# RF_MODULE.net
KiCad netlist of a schematic drawn in Altium Designer
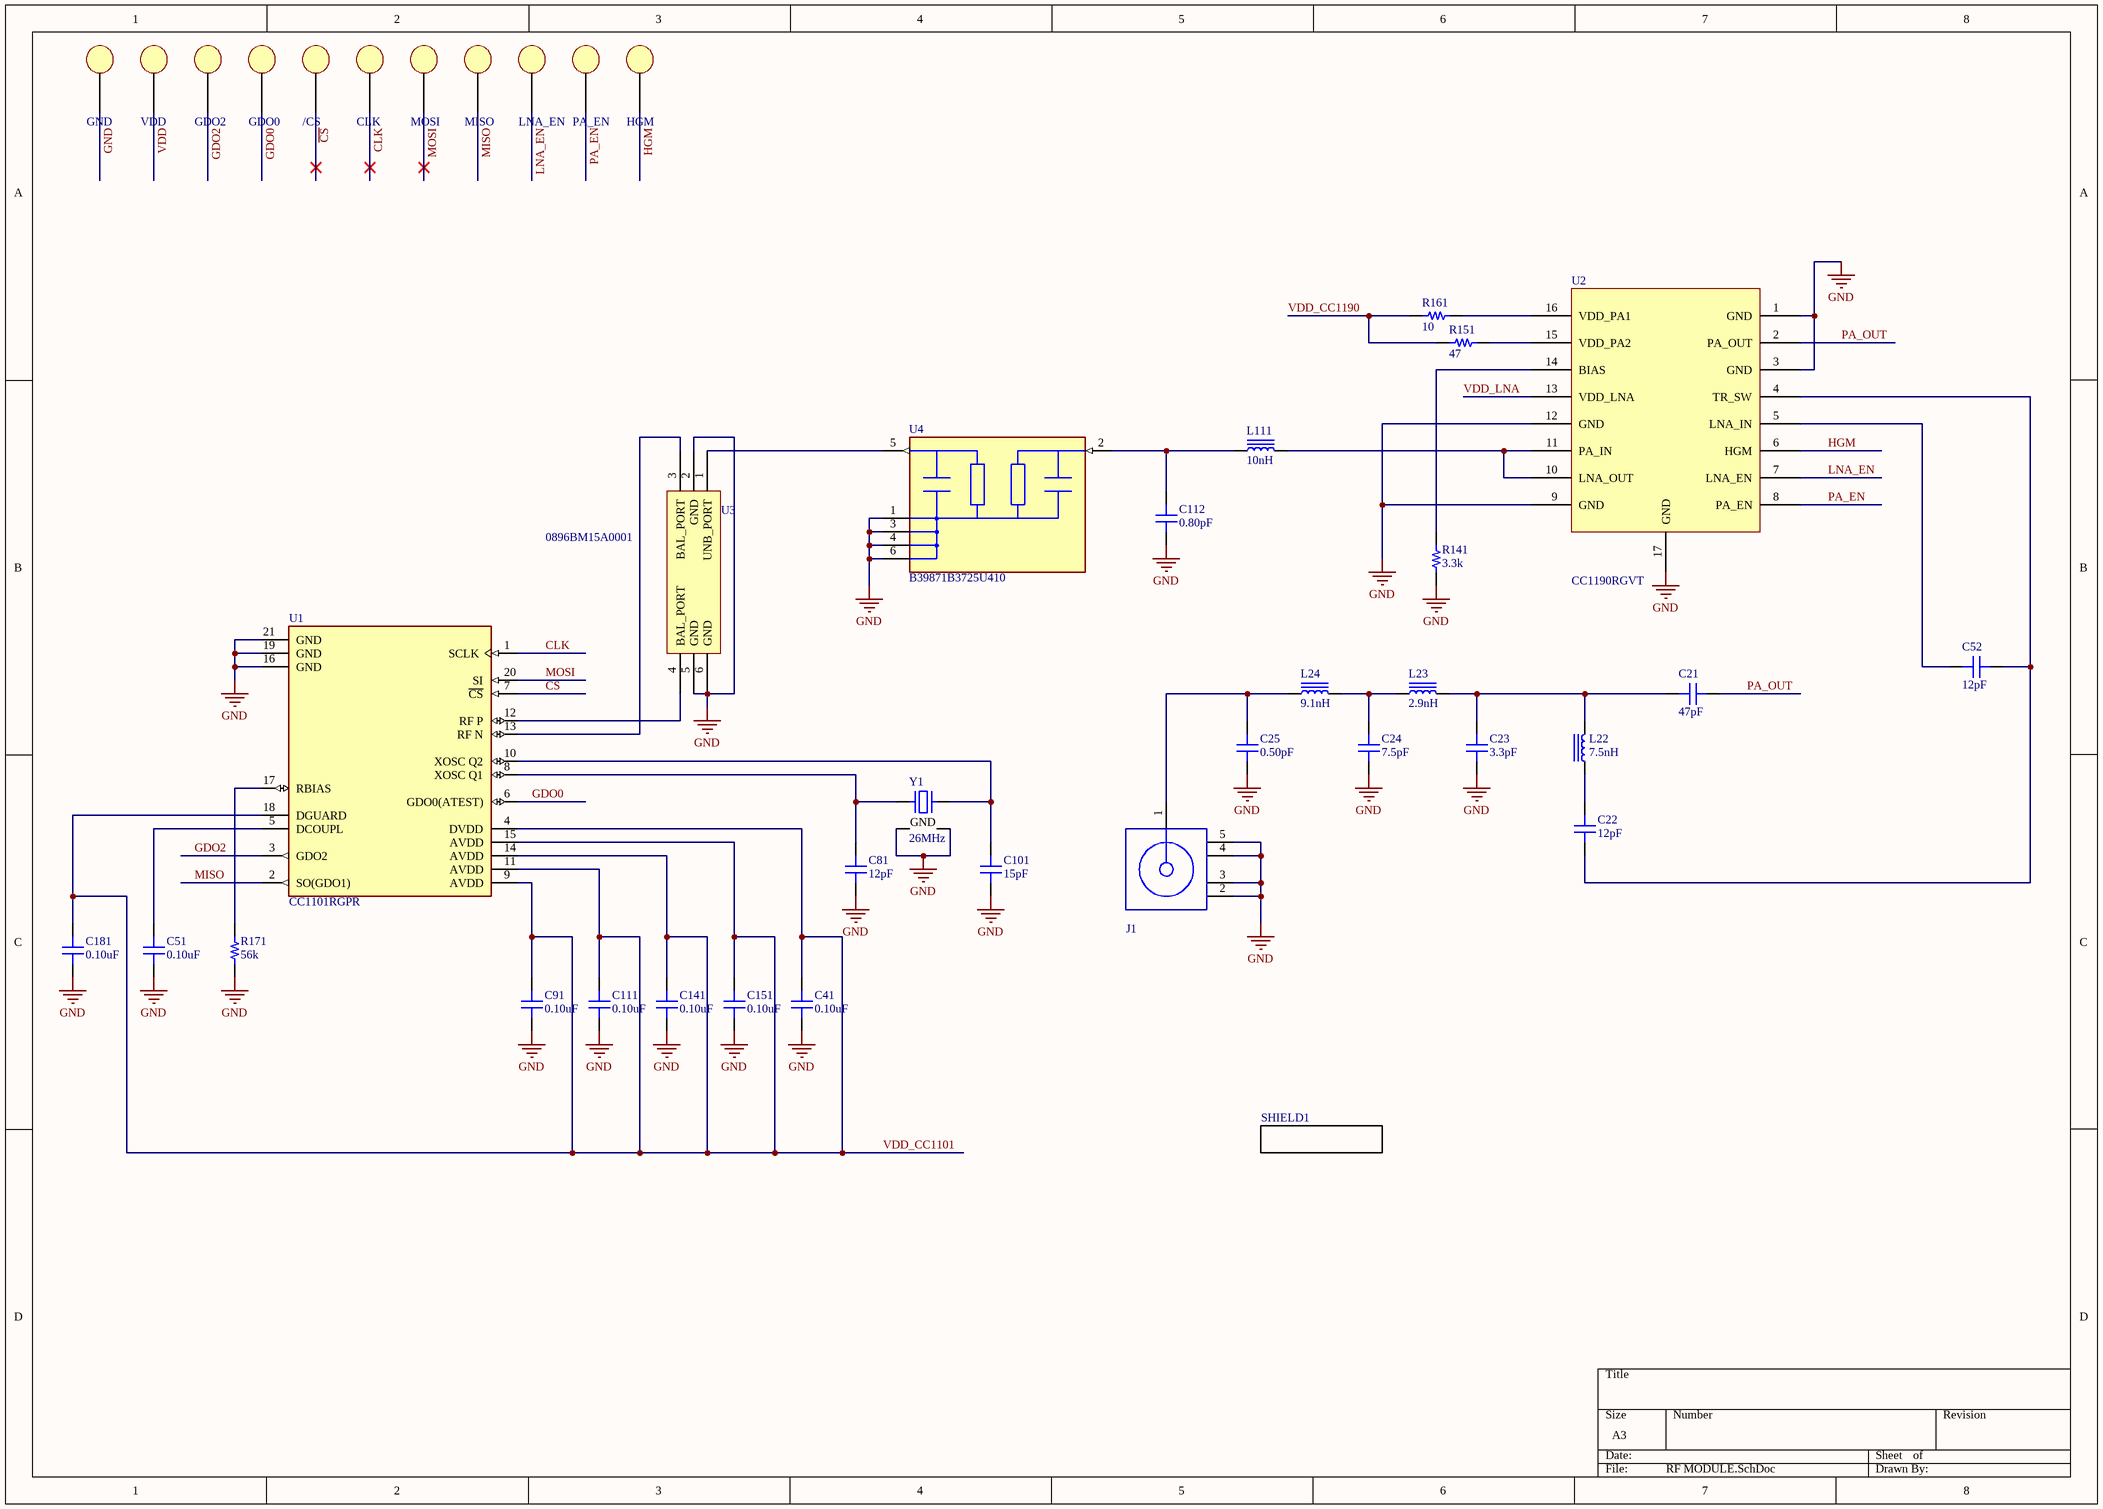
[diagram p0: RF MODULE.SchDoc]

(export (version "E")
  (design (tool "Eeschema 10.0.6"))
  (components
    (comp (ref "/CS")
      (value "Castellation")
      (footprint "Castellation")
      (libsource (lib "MyLibrary") (part "Castellation"))
    )
    (comp (ref "C21")
      (value "47pF")
      (footprint "CAP 0402/1005")
      (description "CAP CER 47PF 50V NP0 0402")
      (fields
        (field (name "PART NUMBER") "GRM1555C1H470JA01D")
        (field (name "MANUFACTURER") "Murata Electronics North America")
      )
      (libsource (lib "Celestial Library Database") (part "Capacitor"))
    )
    (comp (ref "C22")
      (value "12pF")
      (footprint "CAP 0402/1005")
      (description "CAP CER 12PF 50V NP0 0402")
      (fields
        (field (name "PART NUMBER") "GRM1555C1H120JA01D")
        (field (name "MANUFACTURER") "Murata Electronics North America")
      )
      (libsource (lib "Celestial Library Database") (part "Capacitor"))
    )
    (comp (ref "C23")
      (value "3.3pF")
      (footprint "CAP 0402/1005")
      (description "CAP CER 3.3PF 50V NP0 0402")
      (fields
        (field (name "PART NUMBER") "GRM1555C1H3R3CA01D")
        (field (name "MANUFACTURER") "Murata Electronics North America")
      )
      (libsource (lib "Celestial Library Database") (part "Capacitor"))
    )
    (comp (ref "C24")
      (value "7.5pF")
      (footprint "CAP 0402/1005")
      (description "CAP CER 7.5PF 50V NP0 0402")
      (fields
        (field (name "PART NUMBER") "GRM1555C1H7R5CA01D")
        (field (name "MANUFACTURER") "Murata Electronics North America")
      )
      (libsource (lib "Celestial Library Database") (part "Capacitor"))
    )
    (comp (ref "C25")
      (value "0.50pF")
      (footprint "CAP 0402/1005")
      (description "CAP CER 0.50PF 50V NP0 0402")
      (fields
        (field (name "PART NUMBER") "GRM1555C1HR50BA01D")
        (field (name "MANUFACTURER") "Murata Electronics North America")
      )
      (libsource (lib "Celestial Library Database") (part "Capacitor"))
    )
    (comp (ref "C41")
      (value "0.10uF")
      (footprint "CAP 0402/1005")
      (description "CAP CER 0.1UF 10V X5R 0402")
      (fields
        (field (name "PART NUMBER") "GRM152R61A104KE19D")
        (field (name "MANUFACTURER") "Murata Electronics North America")
      )
      (libsource (lib "Celestial Library Database") (part "Capacitor"))
    )
    (comp (ref "C51")
      (value "0.10uF")
      (footprint "CAP 0402/1005")
      (description "CAP CER 0.1UF 10V X5R 0402")
      (fields
        (field (name "PART NUMBER") "GRM152R61A104KE19D")
        (field (name "MANUFACTURER") "Murata Electronics North America")
      )
      (libsource (lib "Celestial Library Database") (part "Capacitor"))
    )
    (comp (ref "C52")
      (value "12pF")
      (footprint "CAP 0402/1005")
      (description "CAP CER 12PF 50V NP0 0402")
      (fields
        (field (name "PART NUMBER") "GRM1555C1H120FA01D")
        (field (name "MANUFACTURER") "Murata Electronics North America")
      )
      (libsource (lib "Celestial Library Database") (part "Capacitor"))
    )
    (comp (ref "C81")
      (value "12pF")
      (footprint "CAP 0402/1005")
      (description "CAP CER 12PF 50V NP0 0402")
      (fields
        (field (name "PART NUMBER") "GRM1555C1H120JA01D")
        (field (name "MANUFACTURER") "Murata Electronics North America")
      )
      (libsource (lib "Celestial Library Database") (part "Capacitor"))
    )
    (comp (ref "C91")
      (value "0.10uF")
      (footprint "CAP 0402/1005")
      (description "CAP CER 0.1UF 10V X5R 0402")
      (fields
        (field (name "PART NUMBER") "GRM152R61A104KE19D")
        (field (name "MANUFACTURER") "Murata Electronics North America")
      )
      (libsource (lib "Celestial Library Database") (part "Capacitor"))
    )
    (comp (ref "C101")
      (value "15pF")
      (footprint "CAP 0402/1005")
      (description "CAP CER 15PF 50V NP0 0402")
      (fields
        (field (name "PART NUMBER") "GRM1555C1H150JA01D")
        (field (name "MANUFACTURER") "Murata Electronics North America")
      )
      (libsource (lib "Celestial Library Database") (part "Capacitor"))
    )
    (comp (ref "C111")
      (value "0.10uF")
      (footprint "CAP 0402/1005")
      (description "CAP CER 0.1UF 10V X5R 0402")
      (fields
        (field (name "PART NUMBER") "GRM152R61A104KE19D")
        (field (name "MANUFACTURER") "Murata Electronics North America")
      )
      (libsource (lib "Celestial Library Database") (part "Capacitor"))
    )
    (comp (ref "C112")
      (value "0.80pF")
      (footprint "CAP 0402/1005")
      (description "CAP CER 0.80PF 50V NP0 0402")
      (fields
        (field (name "PART NUMBER") "GRM1555C1HR80BA01D")
        (field (name "MANUFACTURER") "Murata Electronics North America")
      )
      (libsource (lib "Celestial Library Database") (part "Capacitor"))
    )
    (comp (ref "C141")
      (value "0.10uF")
      (footprint "CAP 0402/1005")
      (description "CAP CER 0.1UF 10V X5R 0402")
      (fields
        (field (name "PART NUMBER") "GRM152R61A104KE19D")
        (field (name "MANUFACTURER") "Murata Electronics North America")
      )
      (libsource (lib "Celestial Library Database") (part "Capacitor"))
    )
    (comp (ref "C151")
      (value "0.10uF")
      (footprint "CAP 0402/1005")
      (description "CAP CER 0.1UF 10V X5R 0402")
      (fields
        (field (name "PART NUMBER") "GRM152R61A104KE19D")
        (field (name "MANUFACTURER") "Murata Electronics North America")
      )
      (libsource (lib "Celestial Library Database") (part "Capacitor"))
    )
    (comp (ref "C181")
      (value "0.10uF")
      (footprint "CAP 0402/1005")
      (description "CAP CER 0.1UF 10V X5R 0402")
      (fields
        (field (name "PART NUMBER") "GRM152R61A104KE19D")
        (field (name "MANUFACTURER") "Murata Electronics North America")
      )
      (libsource (lib "Celestial Library Database") (part "Capacitor"))
    )
    (comp (ref "CLK")
      (value "Castellation")
      (footprint "Castellation")
      (libsource (lib "MyLibrary") (part "Castellation"))
    )
    (comp (ref "GDO0")
      (value "Castellation")
      (footprint "Castellation")
      (libsource (lib "MyLibrary") (part "Castellation"))
    )
    (comp (ref "GDO2")
      (value "Castellation")
      (footprint "Castellation")
      (libsource (lib "MyLibrary") (part "Castellation"))
    )
    (comp (ref "GND")
      (value "Castellation")
      (footprint "Castellation")
      (libsource (lib "MyLibrary") (part "Castellation"))
    )
    (comp (ref "HGM")
      (value "Castellation")
      (footprint "Castellation")
      (libsource (lib "MyLibrary") (part "Castellation"))
    )
    (comp (ref "J1")
      (value "73251-1150")
      (footprint "Molex_73251-1150_0")
      (description "SMA socket")
      (libsource (lib "MyLibrary") (part "73251-1150"))
    )
    (comp (ref "L22")
      (value "7.5nH")
      (footprint "IND 0402/1005 RF WW")
      (description "FIXED IND 7.5NH 570MA 130 MOHM")
      (fields
        (field (name "PART NUMBER") "LQW15AN7N5G00D")
        (field (name "MANUFACTURER") "Murata Electronics North America")
      )
      (libsource (lib "Celestial Library Database") (part "Inductor"))
    )
    (comp (ref "L23")
      (value "2.9nH")
      (footprint "IND 0402/1005 RF WW")
      (description "FIXED IND 2.9NH 750MA 70 MOHM")
      (fields
        (field (name "PART NUMBER") "LQW15AN2N9B00D")
        (field (name "MANUFACTURER") "Murata Electronics North America")
      )
      (libsource (lib "Celestial Library Database") (part "Inductor"))
    )
    (comp (ref "L24")
      (value "9.1nH")
      (footprint "IND 0402/1005 RF WW")
      (description "FIXED IND 9.1NH 540MA 140 MOHM")
      (fields
        (field (name "PART NUMBER") "LQW15AN9N1G00D")
        (field (name "MANUFACTURER") "Murata Electronics North America")
      )
      (libsource (lib "Celestial Library Database") (part "Inductor"))
    )
    (comp (ref "L111")
      (value "10nH")
      (footprint "IND 0402/1005 RF WW")
      (description "FIXED IND 10NH 500MA 170 MOHM")
      (fields
        (field (name "PART NUMBER") "LQW15AN10NG00D")
        (field (name "MANUFACTURER") "Murata Electronics North America")
      )
      (libsource (lib "Celestial Library Database") (part "Inductor"))
    )
    (comp (ref "LNA_EN")
      (value "Castellation")
      (footprint "Castellation")
      (libsource (lib "MyLibrary") (part "Castellation"))
    )
    (comp (ref "MISO")
      (value "Castellation")
      (footprint "Castellation")
      (libsource (lib "MyLibrary") (part "Castellation"))
    )
    (comp (ref "MOSI")
      (value "Castellation")
      (footprint "Castellation")
      (libsource (lib "MyLibrary") (part "Castellation"))
    )
    (comp (ref "PA_EN")
      (value "Castellation")
      (footprint "Castellation")
      (libsource (lib "MyLibrary") (part "Castellation"))
    )
    (comp (ref "R141")
      (value "3.3k")
      (footprint "RES 0402/1005")
      (description "RES SMD 3.3K OHM 1% 1/10W 0402")
      (fields
        (field (name "PART NUMBER") "ERJ-2RKF3301X")
        (field (name "MANUFACTURER") "Panasonic Electronic Components")
      )
      (libsource (lib "Celestial Library Database") (part "Resistor"))
    )
    (comp (ref "R151")
      (value "47")
      (footprint "RES 0402/1005")
      (description "RES SMD 47 OHM 1% 1/10W 0402")
      (fields
        (field (name "PART NUMBER") "ERJ-2RKF47R0X")
        (field (name "MANUFACTURER") "Panasonic Electronic Components")
      )
      (libsource (lib "Celestial Library Database") (part "Resistor"))
    )
    (comp (ref "R161")
      (value "10")
      (footprint "RES 0402/1005")
      (description "RES SMD 10 OHM 1% 1/10W 0402")
      (fields
        (field (name "PART NUMBER") "ERJ-2RKF10R0X")
        (field (name "MANUFACTURER") "Panasonic Electronic Components")
      )
      (libsource (lib "Celestial Library Database") (part "Resistor"))
    )
    (comp (ref "R171")
      (value "56k")
      (footprint "RES 0402/1005")
      (description "RES SMD 56K OHM 1% 1/10W 0402")
      (fields
        (field (name "PART NUMBER") "ERJ-2RKF5602X")
        (field (name "MANUFACTURER") "Panasonic Electronic Components")
      )
      (libsource (lib "Celestial Library Database") (part "Resistor"))
    )
    (comp (ref "SHIELD1")
      (value "SMS-202F")
      (footprint "SMS-202F")
      (description "RF Shield Frame 0.650\" (16.51mm) X 0.650\" (16.51mm) Surface Mount")
      (fields (field (name "MF") "Laird"))
      (libsource (lib "MyLibrary") (part "SMS-202F"))
    )
    (comp (ref "U1")
      (value "CC1101RGPR")
      (footprint "Texas_Instruments_RGP0020C_0")
      (description "Low-Power Sub-1GHz RF Transceiver 20-QFN -40 to 85")
      (libsource (lib "MyLibrary") (part "CC1101RGPR"))
    )
    (comp (ref "U2")
      (value "CC1190RGVT")
      (footprint "QFN65P400X400X100_HS-17N")
      (description "LNA/PA RF Front End 6.2dB 11.6dB/27.9dB 16-Pin VQFN EP T/R")
      (libsource (lib "MyLibrary") (part "CC1190RGVT"))
    )
    (comp (ref "U3")
      (value "0896BM15A0001")
      (footprint "0896BM15A0001")
      (description "868/915 MHz Impedance Matched/Balun/LPF Integrated Component")
      (libsource (lib "MyLibrary") (part "0896BM15A0001"))
    )
    (comp (ref "U4")
      (value "Filter_TDK_B39871B3725U410_eec")
      (footprint "TDK_B39871B3725U410_0")
      (description "FILTER SAW 869.0MHZ SMD")
      (fields
        (field (name "MANUFACTURER") "TDK")
        (field (name "MOUSER PART NUMBER") "871-B39871B3725U410")
        (field (name "PART NUMBER") "B39871B3725U410")
      )
      (libsource (lib "MyLibrary") (part "Filter_TDK_B39871B3725U410_eec"))
    )
    (comp (ref "VDD")
      (value "Castellation")
      (footprint "Castellation")
      (libsource (lib "MyLibrary") (part "Castellation"))
    )
    (comp (ref "Y1")
      (value "26MHz")
      (footprint "NDK NX2520SA")
      (description "CRYSTAL 26.0000MHZ 10PF SMD")
      (fields (field (name "PART NUMBER") "NX2520SA-26.000000MHZ") (field (name "MANUFACTURER") "NDK"))
      (libsource (lib "Celestial Library Database") (part "NDK Crystal NX2520SA"))
    )
  )
  (nets
    (net (code "1") (name "/CLK") (class "Default")
      (node (ref "CLK") (pin "PIN") (pinfunction "PIN_PIN") (pintype "passive"))
      (node (ref "U1") (pin "1") (pinfunction "SCLK_1") (pintype "input"))
    )
    (net (code "2") (name "/GDO0") (class "Default")
      (node (ref "GDO0") (pin "PIN") (pinfunction "PIN_PIN") (pintype "passive"))
      (node (ref "U1") (pin "6") (pinfunction "GDO0(ATEST)_6") (pintype "bidirectional"))
    )
    (net (code "3") (name "/GDO2") (class "Default")
      (node (ref "GDO2") (pin "PIN") (pinfunction "PIN_PIN") (pintype "passive"))
      (node (ref "U1") (pin "3") (pinfunction "GDO2_3") (pintype "output"))
    )
    (net (code "4") (name "/HGM") (class "Default")
      (node (ref "HGM") (pin "PIN") (pinfunction "PIN_PIN") (pintype "passive"))
      (node (ref "U2") (pin "6") (pinfunction "HGM_6") (pintype "passive"))
    )
    (net (code "5") (name "/LNA_EN") (class "Default")
      (node (ref "LNA_EN") (pin "PIN") (pinfunction "PIN_PIN") (pintype "passive"))
      (node (ref "U2") (pin "7") (pinfunction "LNA_EN_7") (pintype "passive"))
    )
    (net (code "6") (name "/MISO") (class "Default")
      (node (ref "MISO") (pin "PIN") (pinfunction "PIN_PIN") (pintype "passive"))
      (node (ref "U1") (pin "2") (pinfunction "SO(GDO1)_2") (pintype "output"))
    )
    (net (code "7") (name "/MOSI") (class "Default")
      (node (ref "MOSI") (pin "PIN") (pinfunction "PIN_PIN") (pintype "passive"))
      (node (ref "U1") (pin "20") (pinfunction "SI_20") (pintype "input"))
    )
    (net (code "8") (name "/PA_EN") (class "Default")
      (node (ref "PA_EN") (pin "PIN") (pinfunction "PIN_PIN") (pintype "passive"))
      (node (ref "U2") (pin "8") (pinfunction "PA_EN_8") (pintype "passive"))
    )
    (net (code "9") (name "/PA_OUT") (class "Default")
      (node (ref "C21") (pin "2") (pinfunction "2_2") (pintype "passive"))
      (node (ref "U2") (pin "2") (pinfunction "PA_OUT_2") (pintype "passive"))
    )
    (net (code "10") (name "/VDD") (class "Default")
      (node (ref "VDD") (pin "PIN") (pinfunction "PIN_PIN") (pintype "passive"))
    )
    (net (code "11") (name "/VDD_CC1101") (class "Default")
      (node (ref "C111") (pin "2") (pinfunction "2_2") (pintype "passive"))
      (node (ref "C141") (pin "2") (pinfunction "2_2") (pintype "passive"))
      (node (ref "C151") (pin "2") (pinfunction "2_2") (pintype "passive"))
      (node (ref "C181") (pin "2") (pinfunction "2_2") (pintype "passive"))
      (node (ref "C41") (pin "2") (pinfunction "2_2") (pintype "passive"))
      (node (ref "C91") (pin "2") (pinfunction "2_2") (pintype "passive"))
      (node (ref "U1") (pin "11") (pinfunction "AVDD_11") (pintype "power_in"))
      (node (ref "U1") (pin "14") (pinfunction "AVDD_14") (pintype "power_in"))
      (node (ref "U1") (pin "15") (pinfunction "AVDD_15") (pintype "power_in"))
      (node (ref "U1") (pin "18") (pinfunction "DGUARD_18") (pintype "power_in"))
      (node (ref "U1") (pin "4") (pinfunction "DVDD_4") (pintype "power_in"))
      (node (ref "U1") (pin "9") (pinfunction "AVDD_9") (pintype "power_in"))
    )
    (net (code "12") (name "/VDD_CC1190") (class "Default")
      (node (ref "R151") (pin "1") (pinfunction "1_1") (pintype "passive"))
      (node (ref "R161") (pin "1") (pinfunction "1_1") (pintype "passive"))
    )
    (net (code "13") (name "/VDD_LNA") (class "Default")
      (node (ref "U2") (pin "13") (pinfunction "VDD_LNA_13") (pintype "passive"))
    )
    (net (code "14") (name "/~{CS}") (class "Default")
      (node (ref "/CS") (pin "PIN") (pinfunction "PIN_PIN") (pintype "passive"))
      (node (ref "U1") (pin "7") (pinfunction "~{CS}_7") (pintype "input"))
    )
    (net (code "15") (name "GND") (class "Default")
      (node (ref "C101") (pin "1") (pinfunction "1_1") (pintype "passive"))
      (node (ref "C111") (pin "1") (pinfunction "1_1") (pintype "passive"))
      (node (ref "C112") (pin "1") (pinfunction "1_1") (pintype "passive"))
      (node (ref "C141") (pin "1") (pinfunction "1_1") (pintype "passive"))
      (node (ref "C151") (pin "1") (pinfunction "1_1") (pintype "passive"))
      (node (ref "C181") (pin "1") (pinfunction "1_1") (pintype "passive"))
      (node (ref "C23") (pin "1") (pinfunction "1_1") (pintype "passive"))
      (node (ref "C24") (pin "1") (pinfunction "1_1") (pintype "passive"))
      (node (ref "C25") (pin "1") (pinfunction "1_1") (pintype "passive"))
      (node (ref "C41") (pin "1") (pinfunction "1_1") (pintype "passive"))
      (node (ref "C51") (pin "1") (pinfunction "1_1") (pintype "passive"))
      (node (ref "C81") (pin "1") (pinfunction "1_1") (pintype "passive"))
      (node (ref "C91") (pin "1") (pinfunction "1_1") (pintype "passive"))
      (node (ref "GND") (pin "PIN") (pinfunction "PIN_PIN") (pintype "passive"))
      (node (ref "J1") (pin "2") (pinfunction "MNT_1_2") (pintype "passive"))
      (node (ref "J1") (pin "3") (pinfunction "MNT_2_3") (pintype "passive"))
      (node (ref "J1") (pin "4") (pinfunction "MNT_3_4") (pintype "passive"))
      (node (ref "J1") (pin "5") (pinfunction "MNT_4_5") (pintype "passive"))
      (node (ref "R141") (pin "1") (pinfunction "1_1") (pintype "passive"))
      (node (ref "R171") (pin "1") (pinfunction "1_1") (pintype "passive"))
      (node (ref "U1") (pin "16") (pinfunction "GND_16") (pintype "power_in"))
      (node (ref "U1") (pin "19") (pinfunction "GND_19") (pintype "power_in"))
      (node (ref "U1") (pin "21") (pinfunction "GND_21") (pintype "power_in"))
      (node (ref "U2") (pin "1") (pinfunction "GND_1") (pintype "passive"))
      (node (ref "U2") (pin "12") (pinfunction "GND_12") (pintype "passive"))
      (node (ref "U2") (pin "17") (pinfunction "GND_17") (pintype "passive"))
      (node (ref "U2") (pin "3") (pinfunction "GND_3") (pintype "passive"))
      (node (ref "U2") (pin "9") (pinfunction "GND_9") (pintype "passive"))
      (node (ref "U3") (pin "2") (pinfunction "GND_2") (pintype "passive"))
      (node (ref "U3") (pin "5") (pinfunction "GND_5") (pintype "passive"))
      (node (ref "U3") (pin "6") (pinfunction "GND_6") (pintype "passive"))
      (node (ref "U4") (pin "1") (pinfunction "Ground_1") (pintype "power_in"))
      (node (ref "U4") (pin "3") (pinfunction "Ground_3") (pintype "power_in"))
      (node (ref "U4") (pin "4") (pinfunction "Ground_4") (pintype "power_in"))
      (node (ref "U4") (pin "6") (pinfunction "Ground_6") (pintype "power_in"))
      (node (ref "Y1") (pin "2") (pinfunction "GND_2") (pintype "passive"))
      (node (ref "Y1") (pin "4") (pinfunction "GND_4") (pintype "passive"))
    )
    (net (code "16") (name "Net-(C21-Pad1)") (class "Default")
      (node (ref "C21") (pin "1") (pinfunction "1_1") (pintype "passive"))
      (node (ref "C23") (pin "2") (pinfunction "2_2") (pintype "passive"))
      (node (ref "L22") (pin "2") (pinfunction "2_2") (pintype "passive"))
      (node (ref "L23") (pin "2") (pinfunction "2_2") (pintype "passive"))
    )
    (net (code "17") (name "Net-(C22-Pad2)") (class "Default")
      (node (ref "C22") (pin "2") (pinfunction "2_2") (pintype "passive"))
      (node (ref "L22") (pin "1") (pinfunction "1_1") (pintype "passive"))
    )
    (net (code "18") (name "Net-(C24-Pad2)") (class "Default")
      (node (ref "C24") (pin "2") (pinfunction "2_2") (pintype "passive"))
      (node (ref "L23") (pin "1") (pinfunction "1_1") (pintype "passive"))
      (node (ref "L24") (pin "2") (pinfunction "2_2") (pintype "passive"))
    )
    (net (code "19") (name "Net-(C25-Pad2)") (class "Default")
      (node (ref "C25") (pin "2") (pinfunction "2_2") (pintype "passive"))
      (node (ref "J1") (pin "1") (pinfunction "1_1") (pintype "passive"))
      (node (ref "L24") (pin "1") (pinfunction "1_1") (pintype "passive"))
    )
    (net (code "20") (name "Net-(U1-DCOUPL)") (class "Default")
      (node (ref "C51") (pin "2") (pinfunction "2_2") (pintype "passive"))
      (node (ref "U1") (pin "5") (pinfunction "DCOUPL_5") (pintype "power_in"))
    )
    (net (code "21") (name "Net-(U1-RBIAS)") (class "Default")
      (node (ref "R171") (pin "2") (pinfunction "2_2") (pintype "passive"))
      (node (ref "U1") (pin "17") (pinfunction "RBIAS_17") (pintype "bidirectional"))
    )
    (net (code "22") (name "Net-(U1-RF_N)") (class "Default")
      (node (ref "U1") (pin "13") (pinfunction "RF_N_13") (pintype "bidirectional"))
      (node (ref "U3") (pin "3") (pinfunction "BAL_PORT_3") (pintype "passive"))
    )
    (net (code "23") (name "Net-(U1-RF_P)") (class "Default")
      (node (ref "U1") (pin "12") (pinfunction "RF_P_12") (pintype "bidirectional"))
      (node (ref "U3") (pin "4") (pinfunction "BAL_PORT_4") (pintype "passive"))
    )
    (net (code "24") (name "Net-(U1-XOSC_Q1)") (class "Default")
      (node (ref "C81") (pin "2") (pinfunction "2_2") (pintype "passive"))
      (node (ref "U1") (pin "8") (pinfunction "XOSC_Q1_8") (pintype "bidirectional"))
      (node (ref "Y1") (pin "1") (pinfunction "1_1") (pintype "passive"))
    )
    (net (code "25") (name "Net-(U1-XOSC_Q2)") (class "Default")
      (node (ref "C101") (pin "2") (pinfunction "2_2") (pintype "passive"))
      (node (ref "U1") (pin "10") (pinfunction "XOSC_Q2_10") (pintype "bidirectional"))
      (node (ref "Y1") (pin "3") (pinfunction "3_3") (pintype "passive"))
    )
    (net (code "26") (name "Net-(U2-BIAS)") (class "Default")
      (node (ref "R141") (pin "2") (pinfunction "2_2") (pintype "passive"))
      (node (ref "U2") (pin "14") (pinfunction "BIAS_14") (pintype "passive"))
    )
    (net (code "27") (name "Net-(U2-LNA_IN)") (class "Default")
      (node (ref "C52") (pin "1") (pinfunction "1_1") (pintype "passive"))
      (node (ref "U2") (pin "5") (pinfunction "LNA_IN_5") (pintype "passive"))
    )
    (net (code "28") (name "Net-(U2-LNA_OUT)") (class "Default")
      (node (ref "L111") (pin "2") (pinfunction "2_2") (pintype "passive"))
      (node (ref "U2") (pin "10") (pinfunction "LNA_OUT_10") (pintype "passive"))
      (node (ref "U2") (pin "11") (pinfunction "PA_IN_11") (pintype "passive"))
    )
    (net (code "29") (name "Net-(U2-TR_SW)") (class "Default")
      (node (ref "C22") (pin "1") (pinfunction "1_1") (pintype "passive"))
      (node (ref "C52") (pin "2") (pinfunction "2_2") (pintype "passive"))
      (node (ref "U2") (pin "4") (pinfunction "TR_SW_4") (pintype "passive"))
    )
    (net (code "30") (name "Net-(U2-VDD_PA1)") (class "Default")
      (node (ref "R161") (pin "2") (pinfunction "2_2") (pintype "passive"))
      (node (ref "U2") (pin "16") (pinfunction "VDD_PA1_16") (pintype "passive"))
    )
    (net (code "31") (name "Net-(U2-VDD_PA2)") (class "Default")
      (node (ref "R151") (pin "2") (pinfunction "2_2") (pintype "passive"))
      (node (ref "U2") (pin "15") (pinfunction "VDD_PA2_15") (pintype "passive"))
    )
    (net (code "32") (name "Net-(U3-UNB_PORT)") (class "Default")
      (node (ref "U3") (pin "1") (pinfunction "UNB_PORT_1") (pintype "passive"))
      (node (ref "U4") (pin "5") (pinfunction "Output_5") (pintype "output"))
    )
    (net (code "33") (name "Net-(U4-Input)") (class "Default")
      (node (ref "C112") (pin "2") (pinfunction "2_2") (pintype "passive"))
      (node (ref "L111") (pin "1") (pinfunction "1_1") (pintype "passive"))
      (node (ref "U4") (pin "2") (pinfunction "Input_2") (pintype "input"))
    )
  )
)
